# motor_controller.net
KiCad netlist of a schematic drawn in EAGLE
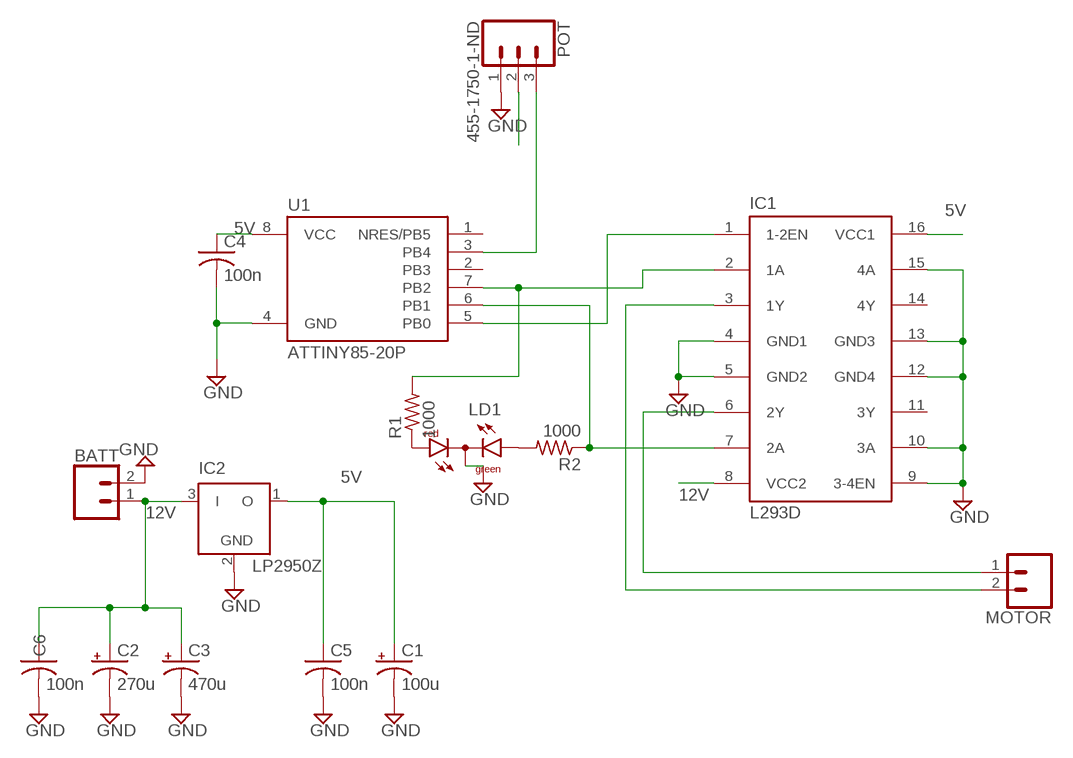
[diagram p0: schematic, sheet 1]

(export (version "E")
  (design (tool "Eeschema 10.0.6"))
  (components
    (comp (ref "BATT")
      (value "CONN_02")
      (footprint "eagle-import:1X02")
      (libsource (lib "eagle-import") (part "CONN_02"))
    )
    (comp (ref "C1")
      (value "100u")
      (footprint "eagle-import:E3,5-10")
      (libsource (lib "eagle-import") (part "CPOL-USE3.5-10"))
    )
    (comp (ref "C2")
      (value "270u")
      (footprint "eagle-import:E3,5-10")
      (libsource (lib "eagle-import") (part "CPOL-USE3.5-10"))
    )
    (comp (ref "C3")
      (value "470u")
      (footprint "eagle-import:E3,5-10")
      (libsource (lib "eagle-import") (part "CPOL-USE3.5-10"))
    )
    (comp (ref "C4")
      (value "100n")
      (footprint "eagle-import:C050-055X075")
      (libsource (lib "eagle-import") (part "C-US050-055X075"))
    )
    (comp (ref "C5")
      (value "100n")
      (footprint "eagle-import:C050-055X075")
      (libsource (lib "eagle-import") (part "C-US050-055X075"))
    )
    (comp (ref "C6")
      (value "100n")
      (footprint "eagle-import:C050-055X075")
      (libsource (lib "eagle-import") (part "C-US050-055X075"))
    )
    (comp (ref "IC1")
      (value "L293D")
      (footprint "eagle-import:DIL16")
      (libsource (lib "eagle-import") (part "L293D"))
    )
    (comp (ref "IC2")
      (value "LP2950Z")
      (footprint "eagle-import:TO92")
      (libsource (lib "eagle-import") (part "LP2950Z"))
    )
    (comp (ref "LD1")
      (value "DUOLED-RG-C")
      (footprint "eagle-import:DUOLED-C-5MM")
      (libsource (lib "eagle-import") (part "DUOLED-RG-C"))
    )
    (comp (ref "MOTOR")
      (value "CONN_02")
      (footprint "eagle-import:1X02")
      (libsource (lib "eagle-import") (part "CONN_02"))
    )
    (comp (ref "POT")
      (value "455-1750-1-ND")
      (footprint "eagle-import:1X03")
      (libsource (lib "eagle-import") (part "CONN_03"))
    )
    (comp (ref "R1")
      (value "1000")
      (footprint "eagle-import:0204_7")
      (libsource (lib "eagle-import") (part "R-US_0204/7"))
    )
    (comp (ref "R2")
      (value "1000")
      (footprint "eagle-import:0204_7")
      (libsource (lib "eagle-import") (part "R-US_0204/7"))
    )
    (comp (ref "U1")
      (value "ATTINY85-20P")
      (footprint "eagle-import:PDIP08_300MIL")
      (libsource (lib "eagle-import") (part "ATTINY85P-20"))
    )
  )
  (nets
    (net (code "1") (name "/5V") (class "Default")
      (node (ref "C1") (pin "+") (pinfunction "+_+") (pintype "passive"))
      (node (ref "C4") (pin "1") (pinfunction "1_1") (pintype "passive"))
      (node (ref "C5") (pin "1") (pinfunction "1_1") (pintype "passive"))
      (node (ref "IC1") (pin "16") (pinfunction "VCC1_16") (pintype "power_in"))
      (node (ref "IC2") (pin "1") (pinfunction "O_1") (pintype "input"))
      (node (ref "POT") (pin "2") (pinfunction "2_2") (pintype "passive"))
      (node (ref "U1") (pin "8") (pinfunction "VCC_8") (pintype "power_in"))
    )
    (net (code "2") (name "/12V") (class "Default")
      (node (ref "BATT") (pin "1") (pinfunction "1_1") (pintype "passive"))
      (node (ref "C2") (pin "+") (pinfunction "+_+") (pintype "passive"))
      (node (ref "C3") (pin "+") (pinfunction "+_+") (pintype "passive"))
      (node (ref "C6") (pin "1") (pinfunction "1_1") (pintype "passive"))
      (node (ref "IC1") (pin "8") (pinfunction "VCC2_8") (pintype "power_in"))
      (node (ref "IC2") (pin "3") (pinfunction "I_3") (pintype "input"))
    )
    (net (code "3") (name "GND") (class "Default")
      (node (ref "BATT") (pin "2") (pinfunction "2_2") (pintype "passive"))
      (node (ref "C1") (pin "-") (pinfunction "-_-") (pintype "passive"))
      (node (ref "C2") (pin "-") (pinfunction "-_-") (pintype "passive"))
      (node (ref "C3") (pin "-") (pinfunction "-_-") (pintype "passive"))
      (node (ref "C4") (pin "2") (pinfunction "2_2") (pintype "passive"))
      (node (ref "C5") (pin "2") (pinfunction "2_2") (pintype "passive"))
      (node (ref "C6") (pin "2") (pinfunction "2_2") (pintype "passive"))
      (node (ref "IC1") (pin "10") (pinfunction "3A_10") (pintype "input"))
      (node (ref "IC1") (pin "12") (pinfunction "GND4_12") (pintype "power_in"))
      (node (ref "IC1") (pin "13") (pinfunction "GND3_13") (pintype "power_in"))
      (node (ref "IC1") (pin "15") (pinfunction "4A_15") (pintype "input"))
      (node (ref "IC1") (pin "4") (pinfunction "GND1_4") (pintype "power_in"))
      (node (ref "IC1") (pin "5") (pinfunction "GND2_5") (pintype "power_in"))
      (node (ref "IC1") (pin "9") (pinfunction "3-4EN_9") (pintype "input"))
      (node (ref "IC2") (pin "2") (pinfunction "GND_2") (pintype "power_in"))
      (node (ref "LD1") (pin "C") (pinfunction "C_C") (pintype "passive"))
      (node (ref "POT") (pin "1") (pinfunction "1_1") (pintype "passive"))
      (node (ref "U1") (pin "4") (pinfunction "GND_4") (pintype "power_in"))
    )
    (net (code "4") (name "Net-(IC1-1-2EN)") (class "Default")
      (node (ref "IC1") (pin "1") (pinfunction "1-2EN_1") (pintype "input"))
      (node (ref "U1") (pin "5") (pinfunction "PB0_5") (pintype "bidirectional"))
    )
    (net (code "5") (name "Net-(IC1-1A)") (class "Default")
      (node (ref "IC1") (pin "2") (pinfunction "1A_2") (pintype "input"))
      (node (ref "R1") (pin "2") (pinfunction "2_2") (pintype "passive"))
      (node (ref "U1") (pin "7") (pinfunction "PB2_7") (pintype "bidirectional"))
    )
    (net (code "6") (name "Net-(IC1-1Y)") (class "Default")
      (node (ref "IC1") (pin "3") (pinfunction "1Y_3") (pintype "output"))
      (node (ref "MOTOR") (pin "2") (pinfunction "2_2") (pintype "passive"))
    )
    (net (code "7") (name "Net-(IC1-2A)") (class "Default")
      (node (ref "IC1") (pin "7") (pinfunction "2A_7") (pintype "input"))
      (node (ref "R2") (pin "1") (pinfunction "1_1") (pintype "passive"))
      (node (ref "U1") (pin "6") (pinfunction "PB1_6") (pintype "bidirectional"))
    )
    (net (code "8") (name "Net-(IC1-2Y)") (class "Default")
      (node (ref "IC1") (pin "6") (pinfunction "2Y_6") (pintype "output"))
      (node (ref "MOTOR") (pin "1") (pinfunction "1_1") (pintype "passive"))
    )
    (net (code "9") (name "Net-(LD1-AG)") (class "Default")
      (node (ref "LD1") (pin "AX") (pinfunction "AG_AX") (pintype "passive"))
      (node (ref "R2") (pin "2") (pinfunction "2_2") (pintype "passive"))
    )
    (net (code "10") (name "Net-(LD1-PadAR)") (class "Default")
      (node (ref "LD1") (pin "AR") (pinfunction "AR_AR") (pintype "passive"))
      (node (ref "R1") (pin "1") (pinfunction "1_1") (pintype "passive"))
    )
    (net (code "11") (name "Net-(U1-PB4)") (class "Default")
      (node (ref "POT") (pin "3") (pinfunction "3_3") (pintype "passive"))
      (node (ref "U1") (pin "3") (pinfunction "PB4_3") (pintype "bidirectional"))
    )
    (net (code "12") (name "unconnected-(IC1-3Y-Pad11)") (class "Default")
      (node (ref "IC1") (pin "11") (pinfunction "3Y_11") (pintype "output"))
    )
    (net (code "13") (name "unconnected-(IC1-4Y-Pad14)") (class "Default")
      (node (ref "IC1") (pin "14") (pinfunction "4Y_14") (pintype "output"))
    )
    (net (code "14") (name "unconnected-(U1-NRES{slash}PB5-Pad1)") (class "Default")
      (node (ref "U1") (pin "1") (pinfunction "NRES/PB5_1") (pintype "bidirectional"))
    )
    (net (code "15") (name "unconnected-(U1-PB3-Pad2)") (class "Default")
      (node (ref "U1") (pin "2") (pinfunction "PB3_2") (pintype "bidirectional"))
    )
  )
)
